# arduino_mega_shield.net
KiCad netlist of a schematic drawn in EAGLE
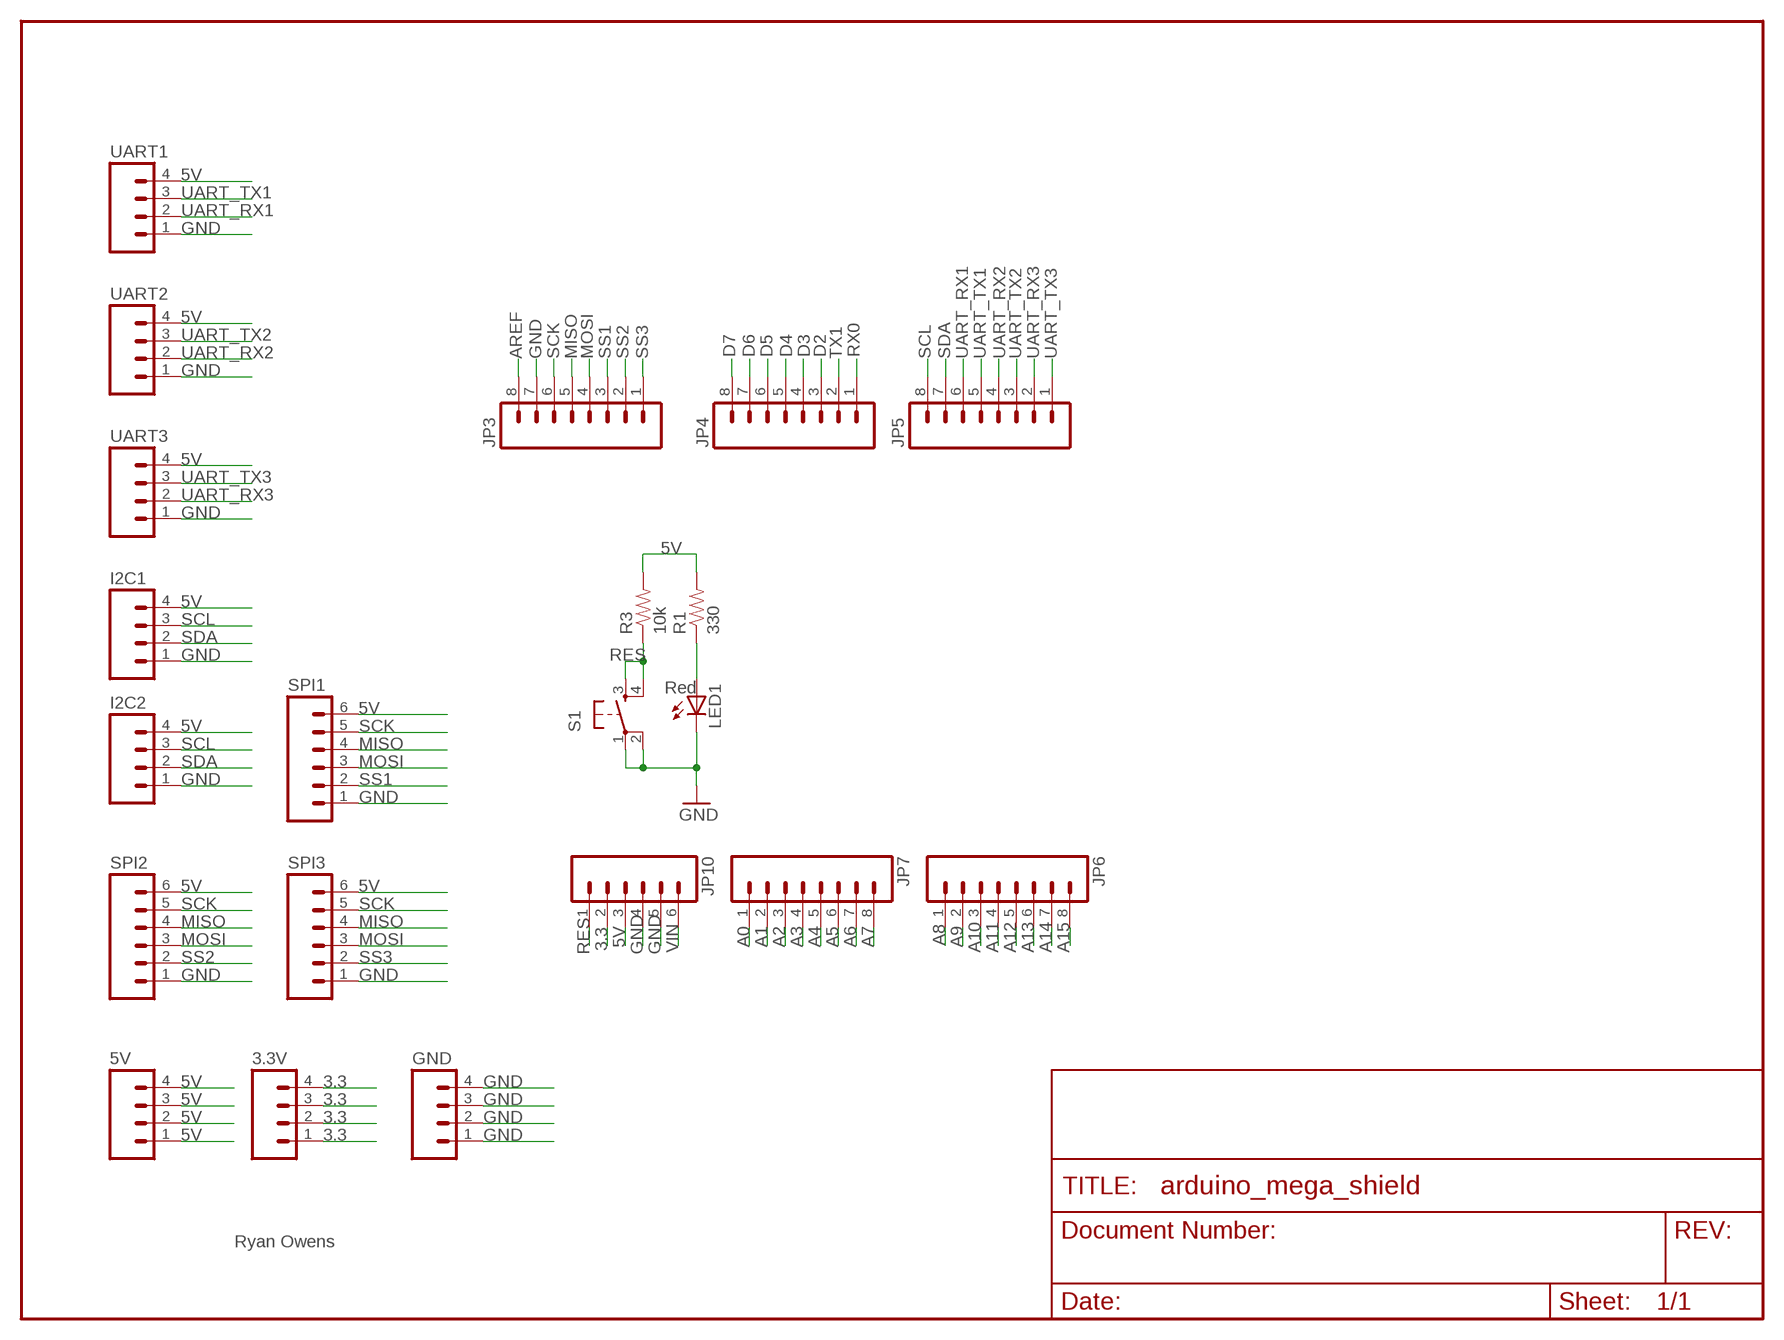
[diagram p0: schematic, sheet 1]

(export (version "E")
  (design (tool "Eeschema 10.0.6"))
  (components
    (comp (ref "3.3V")
      (value "M04LOCK")
      (footprint "eagle-import:1X04_LOCK")
      (libsource (lib "eagle-import") (part "M04LOCK"))
    )
    (comp (ref "5V")
      (value "M04LOCK")
      (footprint "eagle-import:1X04_LOCK")
      (libsource (lib "eagle-import") (part "M04LOCK"))
    )
    (comp (ref "GND")
      (value "M04LOCK")
      (footprint "eagle-import:1X04_LOCK")
      (libsource (lib "eagle-import") (part "M04LOCK"))
    )
    (comp (ref "I2C1")
      (value "M04LOCK")
      (footprint "eagle-import:1X04_LOCK")
      (libsource (lib "eagle-import") (part "M04LOCK"))
    )
    (comp (ref "I2C2")
      (value "M04LOCK")
      (footprint "eagle-import:1X04_LOCK")
      (libsource (lib "eagle-import") (part "M04LOCK"))
    )
    (comp (ref "JP3")
      (value "M08LOCK")
      (footprint "eagle-import:1X08_LOCK")
      (libsource (lib "eagle-import") (part "M08LOCK"))
    )
    (comp (ref "JP4")
      (value "M08LOCK")
      (footprint "eagle-import:1X08_LOCK")
      (libsource (lib "eagle-import") (part "M08LOCK"))
    )
    (comp (ref "JP5")
      (value "M08LOCK")
      (footprint "eagle-import:1X08_LOCK")
      (libsource (lib "eagle-import") (part "M08LOCK"))
    )
    (comp (ref "JP6")
      (value "M08LOCK")
      (footprint "eagle-import:1X08_LOCK")
      (libsource (lib "eagle-import") (part "M08LOCK"))
    )
    (comp (ref "JP7")
      (value "M08LOCK")
      (footprint "eagle-import:1X08_LOCK")
      (libsource (lib "eagle-import") (part "M08LOCK"))
    )
    (comp (ref "JP10")
      (value "M06LOCK")
      (footprint "eagle-import:1X06_LOCK")
      (libsource (lib "eagle-import") (part "M06LOCK"))
    )
    (comp (ref "LED1")
      (value "Red")
      (footprint "eagle-import:LED5MM")
      (libsource (lib "eagle-import") (part "LED5MM"))
    )
    (comp (ref "R1")
      (value "330")
      (footprint "eagle-import:AXIAL-0.3")
      (libsource (lib "eagle-import") (part "RESISTORPTH1"))
    )
    (comp (ref "R3")
      (value "10k")
      (footprint "eagle-import:AXIAL-0.3")
      (libsource (lib "eagle-import") (part "RESISTORPTH1"))
    )
    (comp (ref "S1")
      (value "TAC_SWITCHPTH")
      (footprint "eagle-import:TACTILE-PTH")
      (libsource (lib "eagle-import") (part "TAC_SWITCHPTH"))
    )
    (comp (ref "SPI1")
      (value "M06LOCK")
      (footprint "eagle-import:1X06_LOCK")
      (libsource (lib "eagle-import") (part "SparkFun-Connectors_M06LOCK"))
    )
    (comp (ref "SPI2")
      (value "M06LOCK")
      (footprint "eagle-import:1X06_LOCK")
      (libsource (lib "eagle-import") (part "SparkFun-Connectors_M06LOCK"))
    )
    (comp (ref "SPI3")
      (value "M06LOCK")
      (footprint "eagle-import:1X06_LOCK")
      (libsource (lib "eagle-import") (part "SparkFun-Connectors_M06LOCK"))
    )
    (comp (ref "UART1")
      (value "M04LOCK")
      (footprint "eagle-import:1X04_LOCK")
      (libsource (lib "eagle-import") (part "M04LOCK"))
    )
    (comp (ref "UART2")
      (value "M04LOCK")
      (footprint "eagle-import:1X04_LOCK")
      (libsource (lib "eagle-import") (part "M04LOCK"))
    )
    (comp (ref "UART3")
      (value "M04LOCK")
      (footprint "eagle-import:1X04_LOCK")
      (libsource (lib "eagle-import") (part "M04LOCK"))
    )
  )
  (nets
    (net (code "1") (name "/3.3") (class "Default")
      (node (ref "3.3V") (pin "1") (pinfunction "1_1") (pintype "passive"))
      (node (ref "3.3V") (pin "2") (pinfunction "2_2") (pintype "passive"))
      (node (ref "3.3V") (pin "3") (pinfunction "3_3") (pintype "passive"))
      (node (ref "3.3V") (pin "4") (pinfunction "4_4") (pintype "passive"))
      (node (ref "JP10") (pin "2") (pinfunction "2_2") (pintype "passive"))
    )
    (net (code "2") (name "/5V") (class "Default")
      (node (ref "5V") (pin "1") (pinfunction "1_1") (pintype "passive"))
      (node (ref "5V") (pin "2") (pinfunction "2_2") (pintype "passive"))
      (node (ref "5V") (pin "3") (pinfunction "3_3") (pintype "passive"))
      (node (ref "5V") (pin "4") (pinfunction "4_4") (pintype "passive"))
      (node (ref "I2C1") (pin "4") (pinfunction "4_4") (pintype "passive"))
      (node (ref "I2C2") (pin "4") (pinfunction "4_4") (pintype "passive"))
      (node (ref "JP10") (pin "3") (pinfunction "3_3") (pintype "passive"))
      (node (ref "R1") (pin "P$2") (pinfunction "2_P$2") (pintype "passive"))
      (node (ref "R3") (pin "P$2") (pinfunction "2_P$2") (pintype "passive"))
      (node (ref "SPI1") (pin "6") (pinfunction "6_6") (pintype "passive"))
      (node (ref "SPI2") (pin "6") (pinfunction "6_6") (pintype "passive"))
      (node (ref "SPI3") (pin "6") (pinfunction "6_6") (pintype "passive"))
      (node (ref "UART1") (pin "4") (pinfunction "4_4") (pintype "passive"))
      (node (ref "UART2") (pin "4") (pinfunction "4_4") (pintype "passive"))
      (node (ref "UART3") (pin "4") (pinfunction "4_4") (pintype "passive"))
    )
    (net (code "3") (name "/A0") (class "Default")
      (node (ref "JP7") (pin "1") (pinfunction "1_1") (pintype "passive"))
    )
    (net (code "4") (name "/A1") (class "Default")
      (node (ref "JP7") (pin "2") (pinfunction "2_2") (pintype "passive"))
    )
    (net (code "5") (name "/A2") (class "Default")
      (node (ref "JP7") (pin "3") (pinfunction "3_3") (pintype "passive"))
    )
    (net (code "6") (name "/A3") (class "Default")
      (node (ref "JP7") (pin "4") (pinfunction "4_4") (pintype "passive"))
    )
    (net (code "7") (name "/A4") (class "Default")
      (node (ref "JP7") (pin "5") (pinfunction "5_5") (pintype "passive"))
    )
    (net (code "8") (name "/A5") (class "Default")
      (node (ref "JP7") (pin "6") (pinfunction "6_6") (pintype "passive"))
    )
    (net (code "9") (name "/A6") (class "Default")
      (node (ref "JP7") (pin "7") (pinfunction "7_7") (pintype "passive"))
    )
    (net (code "10") (name "/A7") (class "Default")
      (node (ref "JP7") (pin "8") (pinfunction "8_8") (pintype "passive"))
    )
    (net (code "11") (name "/A8") (class "Default")
      (node (ref "JP6") (pin "1") (pinfunction "1_1") (pintype "passive"))
    )
    (net (code "12") (name "/A9") (class "Default")
      (node (ref "JP6") (pin "2") (pinfunction "2_2") (pintype "passive"))
    )
    (net (code "13") (name "/A10") (class "Default")
      (node (ref "JP6") (pin "3") (pinfunction "3_3") (pintype "passive"))
    )
    (net (code "14") (name "/A11") (class "Default")
      (node (ref "JP6") (pin "4") (pinfunction "4_4") (pintype "passive"))
    )
    (net (code "15") (name "/A12") (class "Default")
      (node (ref "JP6") (pin "5") (pinfunction "5_5") (pintype "passive"))
    )
    (net (code "16") (name "/A13") (class "Default")
      (node (ref "JP6") (pin "6") (pinfunction "6_6") (pintype "passive"))
    )
    (net (code "17") (name "/A14") (class "Default")
      (node (ref "JP6") (pin "7") (pinfunction "7_7") (pintype "passive"))
    )
    (net (code "18") (name "/A15") (class "Default")
      (node (ref "JP6") (pin "8") (pinfunction "8_8") (pintype "passive"))
    )
    (net (code "19") (name "/AREF") (class "Default")
      (node (ref "JP3") (pin "8") (pinfunction "8_8") (pintype "passive"))
    )
    (net (code "20") (name "/D2") (class "Default")
      (node (ref "JP4") (pin "3") (pinfunction "3_3") (pintype "passive"))
    )
    (net (code "21") (name "/D3") (class "Default")
      (node (ref "JP4") (pin "4") (pinfunction "4_4") (pintype "passive"))
    )
    (net (code "22") (name "/D4") (class "Default")
      (node (ref "JP4") (pin "5") (pinfunction "5_5") (pintype "passive"))
    )
    (net (code "23") (name "/D5") (class "Default")
      (node (ref "JP4") (pin "6") (pinfunction "6_6") (pintype "passive"))
    )
    (net (code "24") (name "/D6") (class "Default")
      (node (ref "JP4") (pin "7") (pinfunction "7_7") (pintype "passive"))
    )
    (net (code "25") (name "/D7") (class "Default")
      (node (ref "JP4") (pin "8") (pinfunction "8_8") (pintype "passive"))
    )
    (net (code "26") (name "/MISO") (class "Default")
      (node (ref "JP3") (pin "5") (pinfunction "5_5") (pintype "passive"))
      (node (ref "SPI1") (pin "4") (pinfunction "4_4") (pintype "passive"))
      (node (ref "SPI2") (pin "4") (pinfunction "4_4") (pintype "passive"))
      (node (ref "SPI3") (pin "4") (pinfunction "4_4") (pintype "passive"))
    )
    (net (code "27") (name "/MOSI") (class "Default")
      (node (ref "JP3") (pin "4") (pinfunction "4_4") (pintype "passive"))
      (node (ref "SPI1") (pin "3") (pinfunction "3_3") (pintype "passive"))
      (node (ref "SPI2") (pin "3") (pinfunction "3_3") (pintype "passive"))
      (node (ref "SPI3") (pin "3") (pinfunction "3_3") (pintype "passive"))
    )
    (net (code "28") (name "/RES") (class "Default")
      (node (ref "JP10") (pin "1") (pinfunction "1_1") (pintype "passive"))
      (node (ref "R3") (pin "P$1") (pinfunction "1_P$1") (pintype "passive"))
      (node (ref "S1") (pin "3") (pinfunction "3_3") (pintype "passive"))
      (node (ref "S1") (pin "4") (pinfunction "4_4") (pintype "passive"))
    )
    (net (code "29") (name "/RX0") (class "Default")
      (node (ref "JP4") (pin "1") (pinfunction "1_1") (pintype "passive"))
    )
    (net (code "30") (name "/SCK") (class "Default")
      (node (ref "JP3") (pin "6") (pinfunction "6_6") (pintype "passive"))
      (node (ref "SPI1") (pin "5") (pinfunction "5_5") (pintype "passive"))
      (node (ref "SPI2") (pin "5") (pinfunction "5_5") (pintype "passive"))
      (node (ref "SPI3") (pin "5") (pinfunction "5_5") (pintype "passive"))
    )
    (net (code "31") (name "/SCL") (class "Default")
      (node (ref "I2C1") (pin "3") (pinfunction "3_3") (pintype "passive"))
      (node (ref "I2C2") (pin "3") (pinfunction "3_3") (pintype "passive"))
      (node (ref "JP5") (pin "8") (pinfunction "8_8") (pintype "passive"))
    )
    (net (code "32") (name "/SDA") (class "Default")
      (node (ref "I2C1") (pin "2") (pinfunction "2_2") (pintype "passive"))
      (node (ref "I2C2") (pin "2") (pinfunction "2_2") (pintype "passive"))
      (node (ref "JP5") (pin "7") (pinfunction "7_7") (pintype "passive"))
    )
    (net (code "33") (name "/SS1") (class "Default")
      (node (ref "JP3") (pin "3") (pinfunction "3_3") (pintype "passive"))
      (node (ref "SPI1") (pin "2") (pinfunction "2_2") (pintype "passive"))
    )
    (net (code "34") (name "/SS2") (class "Default")
      (node (ref "JP3") (pin "2") (pinfunction "2_2") (pintype "passive"))
      (node (ref "SPI2") (pin "2") (pinfunction "2_2") (pintype "passive"))
    )
    (net (code "35") (name "/SS3") (class "Default")
      (node (ref "JP3") (pin "1") (pinfunction "1_1") (pintype "passive"))
      (node (ref "SPI3") (pin "2") (pinfunction "2_2") (pintype "passive"))
    )
    (net (code "36") (name "/TX1") (class "Default")
      (node (ref "JP4") (pin "2") (pinfunction "2_2") (pintype "passive"))
    )
    (net (code "37") (name "/UART_RX1") (class "Default")
      (node (ref "JP5") (pin "6") (pinfunction "6_6") (pintype "passive"))
      (node (ref "UART1") (pin "2") (pinfunction "2_2") (pintype "passive"))
    )
    (net (code "38") (name "/UART_RX2") (class "Default")
      (node (ref "JP5") (pin "4") (pinfunction "4_4") (pintype "passive"))
      (node (ref "UART2") (pin "2") (pinfunction "2_2") (pintype "passive"))
    )
    (net (code "39") (name "/UART_RX3") (class "Default")
      (node (ref "JP5") (pin "2") (pinfunction "2_2") (pintype "passive"))
      (node (ref "UART3") (pin "2") (pinfunction "2_2") (pintype "passive"))
    )
    (net (code "40") (name "/UART_TX1") (class "Default")
      (node (ref "JP5") (pin "5") (pinfunction "5_5") (pintype "passive"))
      (node (ref "UART1") (pin "3") (pinfunction "3_3") (pintype "passive"))
    )
    (net (code "41") (name "/UART_TX2") (class "Default")
      (node (ref "JP5") (pin "3") (pinfunction "3_3") (pintype "passive"))
      (node (ref "UART2") (pin "3") (pinfunction "3_3") (pintype "passive"))
    )
    (net (code "42") (name "/UART_TX3") (class "Default")
      (node (ref "JP5") (pin "1") (pinfunction "1_1") (pintype "passive"))
      (node (ref "UART3") (pin "3") (pinfunction "3_3") (pintype "passive"))
    )
    (net (code "43") (name "/VIN") (class "Default")
      (node (ref "JP10") (pin "6") (pinfunction "6_6") (pintype "passive"))
    )
    (net (code "44") (name "GND") (class "Default")
      (node (ref "GND") (pin "1") (pinfunction "1_1") (pintype "passive"))
      (node (ref "GND") (pin "2") (pinfunction "2_2") (pintype "passive"))
      (node (ref "GND") (pin "3") (pinfunction "3_3") (pintype "passive"))
      (node (ref "GND") (pin "4") (pinfunction "4_4") (pintype "passive"))
      (node (ref "I2C1") (pin "1") (pinfunction "1_1") (pintype "passive"))
      (node (ref "I2C2") (pin "1") (pinfunction "1_1") (pintype "passive"))
      (node (ref "JP10") (pin "4") (pinfunction "4_4") (pintype "passive"))
      (node (ref "JP10") (pin "5") (pinfunction "5_5") (pintype "passive"))
      (node (ref "JP3") (pin "7") (pinfunction "7_7") (pintype "passive"))
      (node (ref "LED1") (pin "K") (pinfunction "C_K") (pintype "passive"))
      (node (ref "S1") (pin "1") (pinfunction "1_1") (pintype "passive"))
      (node (ref "S1") (pin "2") (pinfunction "2_2") (pintype "passive"))
      (node (ref "SPI1") (pin "1") (pinfunction "1_1") (pintype "passive"))
      (node (ref "SPI2") (pin "1") (pinfunction "1_1") (pintype "passive"))
      (node (ref "SPI3") (pin "1") (pinfunction "1_1") (pintype "passive"))
      (node (ref "UART1") (pin "1") (pinfunction "1_1") (pintype "passive"))
      (node (ref "UART2") (pin "1") (pinfunction "1_1") (pintype "passive"))
      (node (ref "UART3") (pin "1") (pinfunction "1_1") (pintype "passive"))
    )
    (net (code "45") (name "Net-(R1-1)") (class "Default")
      (node (ref "LED1") (pin "A") (pinfunction "A_A") (pintype "passive"))
      (node (ref "R1") (pin "P$1") (pinfunction "1_P$1") (pintype "passive"))
    )
  )
)
